# DisplayBoardMk1.net
KiCad netlist of a schematic drawn in EAGLE
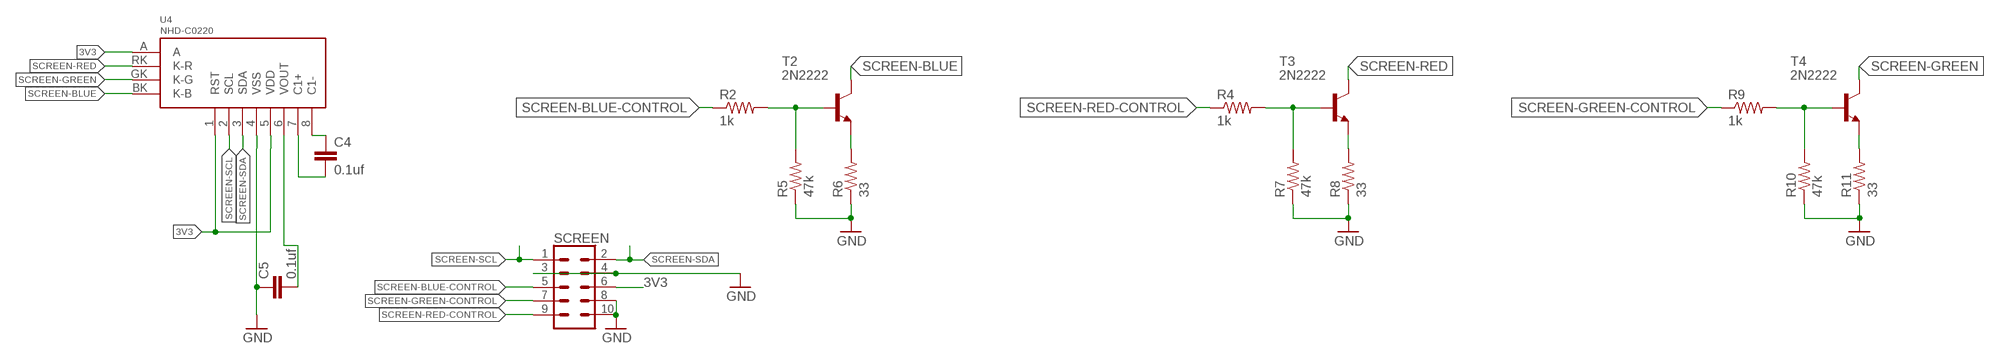
[diagram p0: schematic, sheet 1]

(export (version "E")
  (design (tool "Eeschema 10.0.6"))
  (components
    (comp (ref "C4")
      (value "0.1uf")
      (footprint "eagle-import:C2.5-4")
      (libsource (lib "eagle-import") (part "C2.5/4"))
    )
    (comp (ref "C5")
      (value "0.1uf")
      (footprint "eagle-import:C2.5-4")
      (libsource (lib "eagle-import") (part "C2.5/4"))
    )
    (comp (ref "R2")
      (value "1k")
      (footprint "eagle-import:0207_12")
      (libsource (lib "eagle-import") (part "R-US_0207/12"))
    )
    (comp (ref "R4")
      (value "1k")
      (footprint "eagle-import:0207_12")
      (libsource (lib "eagle-import") (part "R-US_0207/12"))
    )
    (comp (ref "R5")
      (value "47k")
      (footprint "eagle-import:0207_12")
      (libsource (lib "eagle-import") (part "R-US_0207/12"))
    )
    (comp (ref "R6")
      (value "33")
      (footprint "eagle-import:0207_12")
      (libsource (lib "eagle-import") (part "R-US_0207/12"))
    )
    (comp (ref "R7")
      (value "47k")
      (footprint "eagle-import:0207_12")
      (libsource (lib "eagle-import") (part "R-US_0207/12"))
    )
    (comp (ref "R8")
      (value "33")
      (footprint "eagle-import:0207_12")
      (libsource (lib "eagle-import") (part "R-US_0207/12"))
    )
    (comp (ref "R9")
      (value "1k")
      (footprint "eagle-import:0207_12")
      (libsource (lib "eagle-import") (part "R-US_0207/12"))
    )
    (comp (ref "R10")
      (value "47k")
      (footprint "eagle-import:0207_12")
      (libsource (lib "eagle-import") (part "R-US_0207/12"))
    )
    (comp (ref "R11")
      (value "33")
      (footprint "eagle-import:0207_12")
      (libsource (lib "eagle-import") (part "R-US_0207/12"))
    )
    (comp (ref "SCREEN")
      (value "CONN_05X2SHD")
      (footprint "eagle-import:2X5-SHROUDED")
      (libsource (lib "eagle-import") (part "CONN_05X2SHD"))
    )
    (comp (ref "T2")
      (value "2N2222")
      (footprint "eagle-import:TO18")
      (libsource (lib "eagle-import") (part "2N2222"))
    )
    (comp (ref "T3")
      (value "2N2222")
      (footprint "eagle-import:TO18")
      (libsource (lib "eagle-import") (part "2N2222"))
    )
    (comp (ref "T4")
      (value "2N2222")
      (footprint "eagle-import:TO18")
      (libsource (lib "eagle-import") (part "2N2222"))
    )
    (comp (ref "U4")
      (value "NHD‐C0220")
      (footprint "eagle-import:NHD-C0220")
      (libsource (lib "eagle-import") (part "NHD‐C0220"))
    )
  )
  (nets
    (net (code "1") (name "3V3") (class "Default")
      (node (ref "SCREEN") (pin "6") (pinfunction "6_6") (pintype "passive"))
      (node (ref "U4") (pin "1") (pinfunction "RST_1") (pintype "bidirectional"))
      (node (ref "U4") (pin "5") (pinfunction "VDD_5") (pintype "bidirectional"))
      (node (ref "U4") (pin "A") (pinfunction "A_A") (pintype "bidirectional"))
    )
    (net (code "2") (name "GND") (class "Default")
      (node (ref "C5") (pin "1") (pinfunction "1_1") (pintype "passive"))
      (node (ref "R10") (pin "1") (pinfunction "1_1") (pintype "passive"))
      (node (ref "R11") (pin "1") (pinfunction "1_1") (pintype "passive"))
      (node (ref "R5") (pin "1") (pinfunction "1_1") (pintype "passive"))
      (node (ref "R6") (pin "1") (pinfunction "1_1") (pintype "passive"))
      (node (ref "R7") (pin "1") (pinfunction "1_1") (pintype "passive"))
      (node (ref "R8") (pin "1") (pinfunction "1_1") (pintype "passive"))
      (node (ref "SCREEN") (pin "10") (pinfunction "10_10") (pintype "passive"))
      (node (ref "SCREEN") (pin "3") (pinfunction "3_3") (pintype "passive"))
      (node (ref "SCREEN") (pin "4") (pinfunction "4_4") (pintype "passive"))
      (node (ref "SCREEN") (pin "8") (pinfunction "8_8") (pintype "passive"))
      (node (ref "U4") (pin "4") (pinfunction "VSS_4") (pintype "bidirectional"))
    )
    (net (code "3") (name "Net-(T2-B)") (class "Default")
      (node (ref "R2") (pin "2") (pinfunction "2_2") (pintype "passive"))
      (node (ref "R5") (pin "2") (pinfunction "2_2") (pintype "passive"))
      (node (ref "T2") (pin "2") (pinfunction "B_2") (pintype "passive"))
    )
    (net (code "4") (name "Net-(T2-E)") (class "Default")
      (node (ref "R6") (pin "2") (pinfunction "2_2") (pintype "passive"))
      (node (ref "T2") (pin "1") (pinfunction "E_1") (pintype "passive"))
    )
    (net (code "5") (name "Net-(T3-B)") (class "Default")
      (node (ref "R4") (pin "2") (pinfunction "2_2") (pintype "passive"))
      (node (ref "R7") (pin "2") (pinfunction "2_2") (pintype "passive"))
      (node (ref "T3") (pin "2") (pinfunction "B_2") (pintype "passive"))
    )
    (net (code "6") (name "Net-(T3-E)") (class "Default")
      (node (ref "R8") (pin "2") (pinfunction "2_2") (pintype "passive"))
      (node (ref "T3") (pin "1") (pinfunction "E_1") (pintype "passive"))
    )
    (net (code "7") (name "Net-(T4-B)") (class "Default")
      (node (ref "R10") (pin "2") (pinfunction "2_2") (pintype "passive"))
      (node (ref "R9") (pin "2") (pinfunction "2_2") (pintype "passive"))
      (node (ref "T4") (pin "2") (pinfunction "B_2") (pintype "passive"))
    )
    (net (code "8") (name "Net-(T4-E)") (class "Default")
      (node (ref "R11") (pin "2") (pinfunction "2_2") (pintype "passive"))
      (node (ref "T4") (pin "1") (pinfunction "E_1") (pintype "passive"))
    )
    (net (code "9") (name "Net-(U4-C1+)") (class "Default")
      (node (ref "C4") (pin "2") (pinfunction "2_2") (pintype "passive"))
      (node (ref "U4") (pin "7") (pinfunction "C1+_7") (pintype "bidirectional"))
    )
    (net (code "10") (name "Net-(U4-C1-)") (class "Default")
      (node (ref "C4") (pin "1") (pinfunction "1_1") (pintype "passive"))
      (node (ref "U4") (pin "8") (pinfunction "C1-_8") (pintype "bidirectional"))
    )
    (net (code "11") (name "Net-(U4-VOUT)") (class "Default")
      (node (ref "C5") (pin "2") (pinfunction "2_2") (pintype "passive"))
      (node (ref "U4") (pin "6") (pinfunction "VOUT_6") (pintype "bidirectional"))
    )
    (net (code "12") (name "SCREEN-BLUE") (class "Default")
      (node (ref "T2") (pin "3") (pinfunction "C_3") (pintype "passive"))
      (node (ref "U4") (pin "BK") (pinfunction "K-B_BK") (pintype "bidirectional"))
    )
    (net (code "13") (name "SCREEN-BLUE-CONTROL") (class "Default")
      (node (ref "R2") (pin "1") (pinfunction "1_1") (pintype "passive"))
      (node (ref "SCREEN") (pin "5") (pinfunction "5_5") (pintype "passive"))
    )
    (net (code "14") (name "SCREEN-GREEN") (class "Default")
      (node (ref "T4") (pin "3") (pinfunction "C_3") (pintype "passive"))
      (node (ref "U4") (pin "GK") (pinfunction "K-G_GK") (pintype "bidirectional"))
    )
    (net (code "15") (name "SCREEN-GREEN-CONTROL") (class "Default")
      (node (ref "R9") (pin "1") (pinfunction "1_1") (pintype "passive"))
      (node (ref "SCREEN") (pin "7") (pinfunction "7_7") (pintype "passive"))
    )
    (net (code "16") (name "SCREEN-RED") (class "Default")
      (node (ref "T3") (pin "3") (pinfunction "C_3") (pintype "passive"))
      (node (ref "U4") (pin "RK") (pinfunction "K-R_RK") (pintype "bidirectional"))
    )
    (net (code "17") (name "SCREEN-RED-CONTROL") (class "Default")
      (node (ref "R4") (pin "1") (pinfunction "1_1") (pintype "passive"))
      (node (ref "SCREEN") (pin "9") (pinfunction "9_9") (pintype "passive"))
    )
    (net (code "18") (name "SCREEN-SCL") (class "Default")
      (node (ref "SCREEN") (pin "1") (pinfunction "1_1") (pintype "passive"))
      (node (ref "U4") (pin "2") (pinfunction "SCL_2") (pintype "bidirectional"))
    )
    (net (code "19") (name "SCREEN-SDA") (class "Default")
      (node (ref "SCREEN") (pin "2") (pinfunction "2_2") (pintype "passive"))
      (node (ref "U4") (pin "3") (pinfunction "SDA_3") (pintype "bidirectional"))
    )
  )
)
